# 3-Fuses.net
KiCad netlist of a schematic drawn in Altium Designer
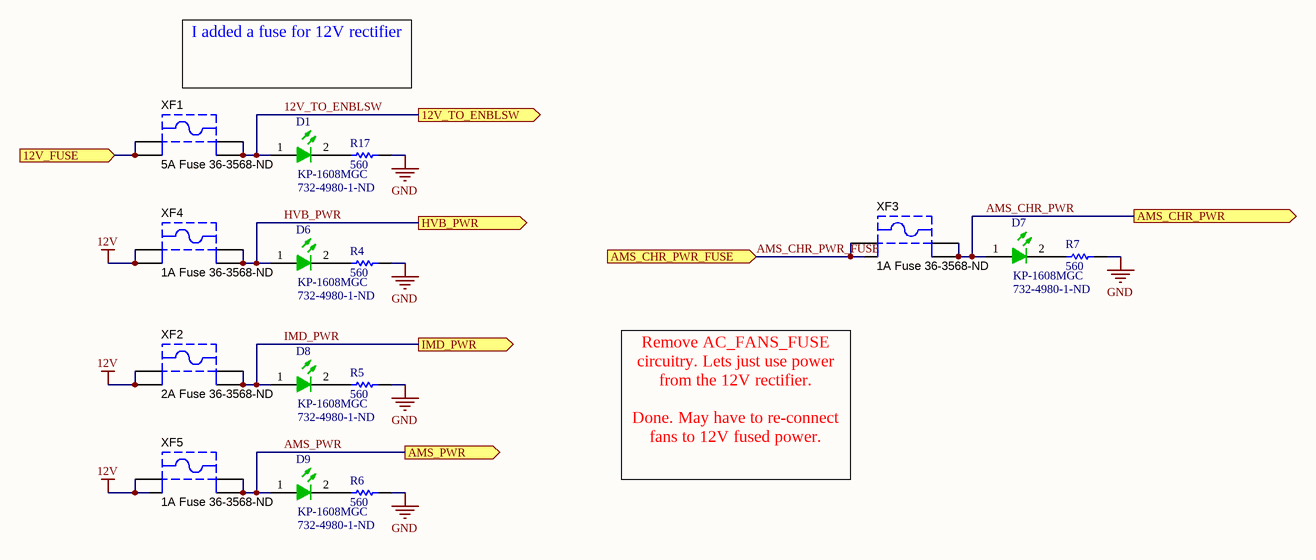
[diagram p0: 3-Fuses.SchDoc]

(export (version "E")
  (design (tool "Eeschema 10.0.6"))
  (components
    (comp (ref "D1")
      (value "KP-1608MGC")
      (footprint "KING-0603LED_GREEN_V")
      (description "LED, SMT, 0603(1608), 1.1mm thickness, Green")
      (fields
        (field (name "MANUFACTURER") "Kingbright")
        (field (name "SUPPLIER PART NUMBER 1") "732-4980-1-ND")
      )
      (libsource (lib "Altium Content Vault") (part "KING-LED-GREEN-A1K2-2"))
    )
    (comp (ref "D6")
      (value "KP-1608MGC")
      (footprint "KING-0603LED_GREEN_V")
      (description "LED, SMT, 0603(1608), 1.1mm thickness, Green")
      (fields
        (field (name "MANUFACTURER") "Kingbright")
        (field (name "SUPPLIER PART NUMBER 1") "732-4980-1-ND")
      )
      (libsource (lib "Altium Content Vault") (part "KING-LED-GREEN-A1K2-2"))
    )
    (comp (ref "D7")
      (value "KP-1608MGC")
      (footprint "KING-0603LED_GREEN_V")
      (description "LED, SMT, 0603(1608), 1.1mm thickness, Green")
      (fields
        (field (name "MANUFACTURER") "Kingbright")
        (field (name "SUPPLIER PART NUMBER 1") "732-4980-1-ND")
      )
      (libsource (lib "Altium Content Vault") (part "KING-LED-GREEN-A1K2-2"))
    )
    (comp (ref "D8")
      (value "KP-1608MGC")
      (footprint "KING-0603LED_GREEN_V")
      (description "LED, SMT, 0603(1608), 1.1mm thickness, Green")
      (fields
        (field (name "MANUFACTURER") "Kingbright")
        (field (name "SUPPLIER PART NUMBER 1") "732-4980-1-ND")
      )
      (libsource (lib "Altium Content Vault") (part "KING-LED-GREEN-A1K2-2"))
    )
    (comp (ref "D9")
      (value "KP-1608MGC")
      (footprint "KING-0603LED_GREEN_V")
      (description "LED, SMT, 0603(1608), 1.1mm thickness, Green")
      (fields
        (field (name "MANUFACTURER") "Kingbright")
        (field (name "SUPPLIER PART NUMBER 1") "732-4980-1-ND")
      )
      (libsource (lib "Altium Content Vault") (part "KING-LED-GREEN-A1K2-2"))
    )
    (comp (ref "R4")
      (value "560")
      (footprint "RESC0603(1608)_L")
      (description "0603 (1608 Metric) Chip Resistor")
      (libsource (lib "Altium Content Vault") (part "RES_3"))
    )
    (comp (ref "R5")
      (value "560")
      (footprint "RESC0603(1608)_L")
      (description "0603 (1608 Metric) Chip Resistor")
      (libsource (lib "Altium Content Vault") (part "RES_3"))
    )
    (comp (ref "R6")
      (value "560")
      (footprint "RESC0603(1608)_L")
      (description "0603 (1608 Metric) Chip Resistor")
      (libsource (lib "Altium Content Vault") (part "RES_3"))
    )
    (comp (ref "R7")
      (value "560")
      (footprint "RESC0603(1608)_L")
      (description "0603 (1608 Metric) Chip Resistor")
      (libsource (lib "Altium Content Vault") (part "RES_3"))
    )
    (comp (ref "R17")
      (value "560")
      (footprint "RESC0603(1608)_L")
      (description "0603 (1608 Metric) Chip Resistor")
      (libsource (lib "Altium Content Vault") (part "RES_3"))
    )
    (comp (ref "XF1")
      (value "5A Fuse 36-3568-ND")
      (footprint "KSTN-3568_V")
      (description "Fuse Holder, 20 A, 500 V, -50 to 145 degC, 4-Pin THD, RoHS")
      (fields (field (name "MANUFACTURER") "Keystone"))
      (libsource (lib "Altium Content Vault") (part "FUSE_HOLDER-4"))
    )
    (comp (ref "XF2")
      (value "2A Fuse 36-3568-ND")
      (footprint "KSTN-3568_V")
      (description "Fuse Holder, 20 A, 500 V, -50 to 145 degC, 4-Pin THD, RoHS")
      (fields (field (name "MANUFACTURER") "Keystone"))
      (libsource (lib "Altium Content Vault") (part "FUSE_HOLDER-4"))
    )
    (comp (ref "XF3")
      (value "1A Fuse 36-3568-ND")
      (footprint "KSTN-3568_V")
      (description "Fuse Holder, 20 A, 500 V, -50 to 145 degC, 4-Pin THD, RoHS")
      (fields (field (name "MANUFACTURER") "Keystone"))
      (libsource (lib "Altium Content Vault") (part "FUSE_HOLDER-4"))
    )
    (comp (ref "XF4")
      (value "1A Fuse 36-3568-ND")
      (footprint "KSTN-3568_V")
      (description "Fuse Holder, 20 A, 500 V, -50 to 145 degC, 4-Pin THD, RoHS")
      (fields (field (name "MANUFACTURER") "Keystone"))
      (libsource (lib "Altium Content Vault") (part "FUSE_HOLDER-4"))
    )
    (comp (ref "XF5")
      (value "1A Fuse 36-3568-ND")
      (footprint "KSTN-3568_V")
      (description "Fuse Holder, 20 A, 500 V, -50 to 145 degC, 4-Pin THD, RoHS")
      (fields (field (name "MANUFACTURER") "Keystone"))
      (libsource (lib "Altium Content Vault") (part "FUSE_HOLDER-4"))
    )
  )
  (nets
    (net (code "1") (name "/12V_FUSE") (class "Default")
      (node (ref "XF1") (pin "1") (pinfunction "1_1") (pintype "passive"))
      (node (ref "XF1") (pin "2") (pinfunction "2_2") (pintype "passive"))
    )
    (net (code "2") (name "/12V_TO_ENBLSW") (class "Default")
      (node (ref "D1") (pin "1") (pinfunction "A_1") (pintype "passive"))
      (node (ref "XF1") (pin "3") (pinfunction "3_3") (pintype "passive"))
      (node (ref "XF1") (pin "4") (pinfunction "4_4") (pintype "passive"))
    )
    (net (code "3") (name "/AMS_CHR_PWR") (class "Default")
      (node (ref "D7") (pin "1") (pinfunction "A_1") (pintype "passive"))
      (node (ref "XF3") (pin "3") (pinfunction "3_3") (pintype "passive"))
      (node (ref "XF3") (pin "4") (pinfunction "4_4") (pintype "passive"))
    )
    (net (code "4") (name "/AMS_CHR_PWR_FUSE") (class "Default")
      (node (ref "XF3") (pin "1") (pinfunction "1_1") (pintype "passive"))
      (node (ref "XF3") (pin "2") (pinfunction "2_2") (pintype "passive"))
    )
    (net (code "5") (name "/AMS_PWR") (class "Default")
      (node (ref "D9") (pin "1") (pinfunction "A_1") (pintype "passive"))
      (node (ref "XF5") (pin "3") (pinfunction "3_3") (pintype "passive"))
      (node (ref "XF5") (pin "4") (pinfunction "4_4") (pintype "passive"))
    )
    (net (code "6") (name "/HVB_PWR") (class "Default")
      (node (ref "D6") (pin "1") (pinfunction "A_1") (pintype "passive"))
      (node (ref "XF4") (pin "3") (pinfunction "3_3") (pintype "passive"))
      (node (ref "XF4") (pin "4") (pinfunction "4_4") (pintype "passive"))
    )
    (net (code "7") (name "/IMD_PWR") (class "Default")
      (node (ref "D8") (pin "1") (pinfunction "A_1") (pintype "passive"))
      (node (ref "XF2") (pin "3") (pinfunction "3_3") (pintype "passive"))
      (node (ref "XF2") (pin "4") (pinfunction "4_4") (pintype "passive"))
    )
    (net (code "8") (name "12V") (class "Default")
      (node (ref "XF2") (pin "1") (pinfunction "1_1") (pintype "passive"))
      (node (ref "XF2") (pin "2") (pinfunction "2_2") (pintype "passive"))
      (node (ref "XF4") (pin "1") (pinfunction "1_1") (pintype "passive"))
      (node (ref "XF4") (pin "2") (pinfunction "2_2") (pintype "passive"))
      (node (ref "XF5") (pin "1") (pinfunction "1_1") (pintype "passive"))
      (node (ref "XF5") (pin "2") (pinfunction "2_2") (pintype "passive"))
    )
    (net (code "9") (name "GND") (class "Default")
      (node (ref "R17") (pin "2") (pinfunction "2_2") (pintype "passive"))
      (node (ref "R4") (pin "2") (pinfunction "2_2") (pintype "passive"))
      (node (ref "R5") (pin "2") (pinfunction "2_2") (pintype "passive"))
      (node (ref "R6") (pin "2") (pinfunction "2_2") (pintype "passive"))
      (node (ref "R7") (pin "2") (pinfunction "2_2") (pintype "passive"))
    )
    (net (code "10") (name "Net-(D1-K)") (class "Default")
      (node (ref "D1") (pin "2") (pinfunction "K_2") (pintype "passive"))
      (node (ref "R17") (pin "1") (pinfunction "1_1") (pintype "passive"))
    )
    (net (code "11") (name "Net-(D6-K)") (class "Default")
      (node (ref "D6") (pin "2") (pinfunction "K_2") (pintype "passive"))
      (node (ref "R4") (pin "1") (pinfunction "1_1") (pintype "passive"))
    )
    (net (code "12") (name "Net-(D7-K)") (class "Default")
      (node (ref "D7") (pin "2") (pinfunction "K_2") (pintype "passive"))
      (node (ref "R7") (pin "1") (pinfunction "1_1") (pintype "passive"))
    )
    (net (code "13") (name "Net-(D8-K)") (class "Default")
      (node (ref "D8") (pin "2") (pinfunction "K_2") (pintype "passive"))
      (node (ref "R5") (pin "1") (pinfunction "1_1") (pintype "passive"))
    )
    (net (code "14") (name "Net-(D9-K)") (class "Default")
      (node (ref "D9") (pin "2") (pinfunction "K_2") (pintype "passive"))
      (node (ref "R6") (pin "1") (pinfunction "1_1") (pintype "passive"))
    )
  )
)
